# FrolfLight.net
KiCad netlist of a schematic drawn in Altium Designer
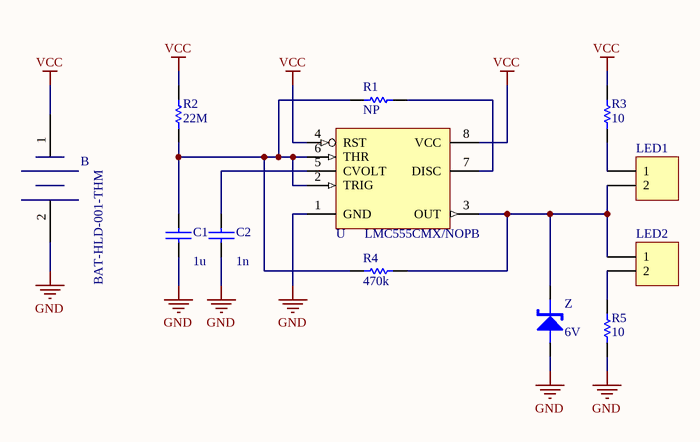
[diagram p0: FrolfLight.SchDoc]

(export (version "E")
  (design (tool "Eeschema 10.0.6"))
  (components
    (comp (ref "B")
      (value "BAT-HLD-001-THM")
      (footprint "Batt")
      (libsource (lib "FrolfLight") (part "Component_1"))
    )
    (comp (ref "C1")
      (value "1u")
      (footprint "0805")
      (fields (field (name "PART NUMBER") "CAP") (field (name "MANUFACTURER") "?"))
      (libsource (lib "EchoflexDatabaseLibrarySVN") (part "CAP"))
    )
    (comp (ref "C2")
      (value "1n")
      (footprint "0603")
      (fields (field (name "PART NUMBER") "CAP") (field (name "MANUFACTURER") "?"))
      (libsource (lib "EchoflexDatabaseLibrarySVN") (part "CAP"))
    )
    (comp (ref "LED1")
      (value "~")
      (footprint "HDR1X2")
      (description "Header, 2-Pin")
      (fields (field (name "PUBLISHER") "Altium Limited"))
      (libsource (lib "Miscellaneous Connectors") (part "Header 2"))
    )
    (comp (ref "LED2")
      (value "~")
      (footprint "HDR1X2")
      (description "Header, 2-Pin")
      (fields (field (name "PUBLISHER") "Altium Limited"))
      (libsource (lib "Miscellaneous Connectors") (part "Header 2"))
    )
    (comp (ref "R1")
      (value "NP")
      (footprint "0603")
      (description "Resistor")
      (fields
        (field (name "PART NUMBER") "Res1")
        (field (name "MANUFACTURER") "?")
        (field (name "PUBLISHER") "Altium Limited")
      )
      (libsource (lib "EchoflexDatabaseLibrarySVN") (part "Res1"))
    )
    (comp (ref "R2")
      (value "22M")
      (footprint "0603")
      (description "Resistor")
      (fields
        (field (name "PART NUMBER") "Res1")
        (field (name "MANUFACTURER") "?")
        (field (name "PUBLISHER") "Altium Limited")
      )
      (libsource (lib "EchoflexDatabaseLibrarySVN") (part "Res1"))
    )
    (comp (ref "R3")
      (value "10")
      (footprint "0603")
      (description "Resistor")
      (fields
        (field (name "PART NUMBER") "Res1")
        (field (name "MANUFACTURER") "?")
        (field (name "PUBLISHER") "Altium Limited")
      )
      (libsource (lib "EchoflexDatabaseLibrarySVN") (part "Res1"))
    )
    (comp (ref "R4")
      (value "470k")
      (footprint "0603")
      (description "Resistor")
      (fields
        (field (name "PART NUMBER") "Res1")
        (field (name "MANUFACTURER") "?")
        (field (name "PUBLISHER") "Altium Limited")
      )
      (libsource (lib "EchoflexDatabaseLibrarySVN") (part "Res1"))
    )
    (comp (ref "R5")
      (value "10")
      (footprint "0603")
      (description "Resistor")
      (fields
        (field (name "PART NUMBER") "Res1")
        (field (name "MANUFACTURER") "?")
        (field (name "PUBLISHER") "Altium Limited")
      )
      (libsource (lib "EchoflexDatabaseLibrarySVN") (part "Res1"))
    )
    (comp (ref "U") (value "LMC555CMX/NOPB") (footprint "555") (libsource (lib "FrolfLight") (part "555")))
    (comp (ref "Z")
      (value "6V")
      (footprint "SOT-23_DIODE")
      (fields (field (name "PART NUMBER") "DIODE, ZENER") (field (name "MANUFACTURER") "?"))
      (libsource (lib "EchoflexDatabaseLibrarySVN") (part "DIODE, ZENER"))
    )
  )
  (nets
    (net (code "1") (name "GND") (class "Default")
      (node (ref "B") (pin "2") (pinfunction "-_2") (pintype "passive"))
      (node (ref "C1") (pin "2") (pintype "passive"))
      (node (ref "C2") (pin "2") (pintype "passive"))
      (node (ref "R5") (pin "1") (pinfunction "1_1") (pintype "passive"))
      (node (ref "U") (pin "1") (pinfunction "GND_1") (pintype "power_in"))
      (node (ref "Z") (pin "A") (pintype "passive"))
    )
    (net (code "2") (name "Net-(LED1-Pad1)") (class "Default")
      (node (ref "LED1") (pin "1") (pinfunction "1_1") (pintype "passive"))
      (node (ref "R3") (pin "2") (pinfunction "2_2") (pintype "passive"))
    )
    (net (code "3") (name "Net-(LED2-Pad2)") (class "Default")
      (node (ref "LED2") (pin "2") (pinfunction "2_2") (pintype "passive"))
      (node (ref "R5") (pin "2") (pinfunction "2_2") (pintype "passive"))
    )
    (net (code "4") (name "Net-(U-CVOLT)") (class "Default")
      (node (ref "C2") (pin "1") (pintype "passive"))
      (node (ref "U") (pin "5") (pinfunction "CVOLT_5") (pintype "passive"))
    )
    (net (code "5") (name "Net-(U-DISC)") (class "Default")
      (node (ref "R1") (pin "2") (pinfunction "2_2") (pintype "passive"))
      (node (ref "U") (pin "7") (pinfunction "DISC_7") (pintype "open_collector"))
    )
    (net (code "6") (name "Net-(U-OUT)") (class "Default")
      (node (ref "LED1") (pin "2") (pinfunction "2_2") (pintype "passive"))
      (node (ref "LED2") (pin "1") (pinfunction "1_1") (pintype "passive"))
      (node (ref "R4") (pin "2") (pinfunction "2_2") (pintype "passive"))
      (node (ref "U") (pin "3") (pinfunction "OUT_3") (pintype "output"))
      (node (ref "Z") (pin "K") (pintype "passive"))
    )
    (net (code "7") (name "Net-(U-THR)") (class "Default")
      (node (ref "C1") (pin "1") (pintype "passive"))
      (node (ref "R1") (pin "1") (pinfunction "1_1") (pintype "passive"))
      (node (ref "R2") (pin "1") (pinfunction "1_1") (pintype "passive"))
      (node (ref "R4") (pin "1") (pinfunction "1_1") (pintype "passive"))
      (node (ref "U") (pin "2") (pinfunction "TRIG_2") (pintype "input"))
      (node (ref "U") (pin "6") (pinfunction "THR_6") (pintype "input"))
    )
    (net (code "8") (name "VCC") (class "Default")
      (node (ref "B") (pin "1") (pinfunction "+_1") (pintype "passive"))
      (node (ref "R2") (pin "2") (pinfunction "2_2") (pintype "passive"))
      (node (ref "R3") (pin "1") (pinfunction "1_1") (pintype "passive"))
      (node (ref "U") (pin "4") (pinfunction "RST_4") (pintype "input"))
      (node (ref "U") (pin "8") (pinfunction "VCC_8") (pintype "power_in"))
    )
  )
)
